# Current_ACS712.net
KiCad netlist of a schematic drawn in EAGLE
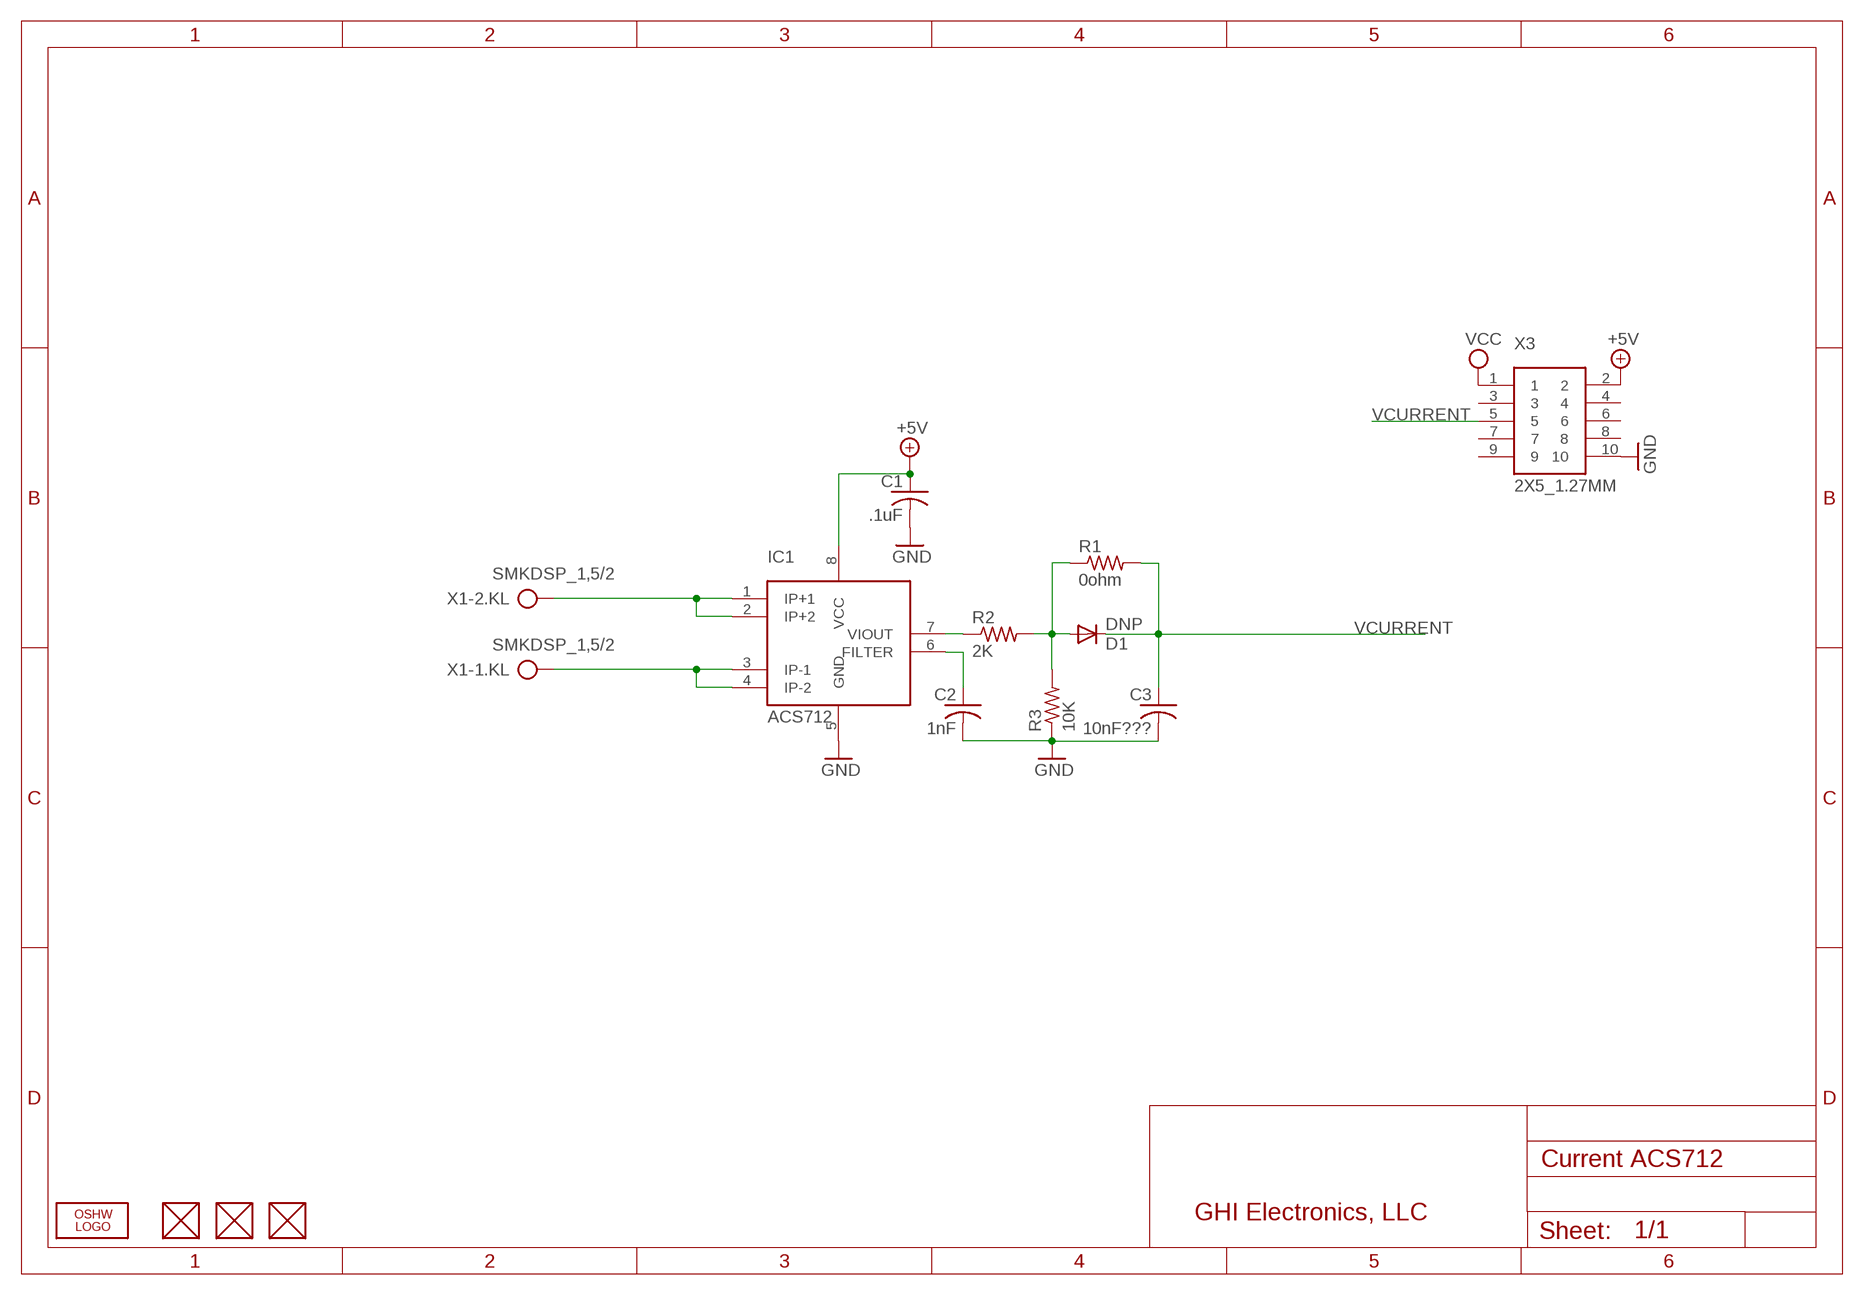
[diagram p0: schematic, sheet 1]

(export (version "E")
  (design (tool "Eeschema 10.0.6"))
  (components
    (comp (ref "C1")
      (value ".1uF")
      (footprint "eagle-import:C0603K")
      (libsource (lib "eagle-import") (part "C-USC0603K"))
    )
    (comp (ref "C2")
      (value "1nF")
      (footprint "eagle-import:C0603K")
      (libsource (lib "eagle-import") (part "C-USC0603K"))
    )
    (comp (ref "C3")
      (value "10nF???")
      (footprint "eagle-import:C0603K")
      (libsource (lib "eagle-import") (part "C-USC0603K"))
    )
    (comp (ref "D1")
      (value "DNP")
      (footprint "eagle-import:SOD323-W")
      (libsource (lib "eagle-import") (part "DIODE-SOD323-W"))
    )
    (comp (ref "FUD1")
      (value "FIDUCIAL")
      (footprint "eagle-import:FIDUCIAL_40MIL")
      (libsource (lib "eagle-import") (part "FIDUCIAL"))
    )
    (comp (ref "FUD2")
      (value "FIDUCIAL")
      (footprint "eagle-import:FIDUCIAL_40MIL")
      (libsource (lib "eagle-import") (part "FIDUCIAL"))
    )
    (comp (ref "FUD3")
      (value "FIDUCIAL")
      (footprint "eagle-import:FIDUCIAL_40MIL")
      (libsource (lib "eagle-import") (part "FIDUCIAL"))
    )
    (comp (ref "IC1")
      (value "ACS712")
      (footprint "eagle-import:SO8")
      (libsource (lib "eagle-import") (part "ACS712"))
    )
    (comp (ref "LOGO2")
      (value "LOGO-OSHW-FILLX0200-NT")
      (footprint "eagle-import:OSHW_FILLX200_NOTEXT")
      (libsource (lib "eagle-import") (part "LOGO-OSHW-FILLX0200-NT"))
    )
    (comp (ref "R1")
      (value "0ohm")
      (footprint "eagle-import:R0603")
      (libsource (lib "eagle-import") (part "R-US_R0603"))
    )
    (comp (ref "R2")
      (value "2K")
      (footprint "eagle-import:R0603")
      (libsource (lib "eagle-import") (part "R-US_R0603"))
    )
    (comp (ref "R3")
      (value "10K")
      (footprint "eagle-import:R0603")
      (libsource (lib "eagle-import") (part "R-US_R0603"))
    )
    (comp (ref "X1")
      (value "SMKDSP_1,5/2")
      (footprint "eagle-import:SMKDSP_1,5_2")
      (libsource (lib "eagle-import") (part "SMKDSP_1,5/2"))
    )
    (comp (ref "X3")
      (value "2X5_1.27MM")
      (footprint "eagle-import:2X5_1.27MM")
      (libsource (lib "eagle-import") (part "2X5_1.27MM"))
    )
  )
  (nets
    (net (code "1") (name "+5V") (class "Default")
      (node (ref "C1") (pin "1") (pinfunction "1_1") (pintype "passive"))
      (node (ref "IC1") (pin "8") (pinfunction "VCC_8") (pintype "bidirectional"))
      (node (ref "X3") (pin "2") (pinfunction "2_2") (pintype "bidirectional"))
    )
    (net (code "2") (name "/VCURRENT") (class "Default")
      (node (ref "C3") (pin "1") (pinfunction "1_1") (pintype "passive"))
      (node (ref "D1") (pin "C") (pinfunction "C_C") (pintype "passive"))
      (node (ref "R1") (pin "2") (pinfunction "2_2") (pintype "passive"))
      (node (ref "X3") (pin "5") (pinfunction "5_5") (pintype "bidirectional"))
    )
    (net (code "3") (name "GND") (class "Default")
      (node (ref "C1") (pin "2") (pinfunction "2_2") (pintype "passive"))
      (node (ref "C2") (pin "2") (pinfunction "2_2") (pintype "passive"))
      (node (ref "C3") (pin "2") (pinfunction "2_2") (pintype "passive"))
      (node (ref "IC1") (pin "5") (pinfunction "GND_5") (pintype "bidirectional"))
      (node (ref "R3") (pin "1") (pinfunction "1_1") (pintype "passive"))
      (node (ref "X3") (pin "10") (pinfunction "10_10") (pintype "bidirectional"))
    )
    (net (code "4") (name "Net-(D1-PadA)") (class "Default")
      (node (ref "D1") (pin "A") (pinfunction "A_A") (pintype "passive"))
      (node (ref "R1") (pin "1") (pinfunction "1_1") (pintype "passive"))
      (node (ref "R2") (pin "2") (pinfunction "2_2") (pintype "passive"))
      (node (ref "R3") (pin "2") (pinfunction "2_2") (pintype "passive"))
    )
    (net (code "5") (name "Net-(IC1-FILTER)") (class "Default")
      (node (ref "C2") (pin "1") (pinfunction "1_1") (pintype "passive"))
      (node (ref "IC1") (pin "6") (pinfunction "FILTER_6") (pintype "bidirectional"))
    )
    (net (code "6") (name "Net-(IC1-IP+1)") (class "Default")
      (node (ref "IC1") (pin "1") (pinfunction "IP+1_1") (pintype "bidirectional"))
      (node (ref "IC1") (pin "2") (pinfunction "IP+2_2") (pintype "bidirectional"))
      (node (ref "X1") (pin "2") (pinfunction "KL_2") (pintype "passive"))
    )
    (net (code "7") (name "Net-(IC1-IP-1)") (class "Default")
      (node (ref "IC1") (pin "3") (pinfunction "IP-1_3") (pintype "bidirectional"))
      (node (ref "IC1") (pin "4") (pinfunction "IP-2_4") (pintype "bidirectional"))
      (node (ref "X1") (pin "1") (pinfunction "KL_1") (pintype "passive"))
    )
    (net (code "8") (name "Net-(IC1-VIOUT)") (class "Default")
      (node (ref "IC1") (pin "7") (pinfunction "VIOUT_7") (pintype "bidirectional"))
      (node (ref "R2") (pin "1") (pinfunction "1_1") (pintype "passive"))
    )
    (net (code "9") (name "VCC") (class "Default")
      (node (ref "X3") (pin "1") (pinfunction "1_1") (pintype "bidirectional"))
    )
    (net (code "10") (name "unconnected-(FUD1-PadP$1)") (class "Default")
      (node (ref "FUD1") (pin "P$1") (pinfunction "P$1_P$1") (pintype "no_connect"))
    )
    (net (code "11") (name "unconnected-(FUD2-PadP$1)") (class "Default")
      (node (ref "FUD2") (pin "P$1") (pinfunction "P$1_P$1") (pintype "no_connect"))
    )
    (net (code "12") (name "unconnected-(FUD3-PadP$1)") (class "Default")
      (node (ref "FUD3") (pin "P$1") (pinfunction "P$1_P$1") (pintype "no_connect"))
    )
    (net (code "13") (name "unconnected-(X3-Pad3)") (class "Default")
      (node (ref "X3") (pin "3") (pinfunction "3_3") (pintype "bidirectional"))
    )
    (net (code "14") (name "unconnected-(X3-Pad4)") (class "Default")
      (node (ref "X3") (pin "4") (pinfunction "4_4") (pintype "bidirectional"))
    )
    (net (code "15") (name "unconnected-(X3-Pad6)") (class "Default")
      (node (ref "X3") (pin "6") (pinfunction "6_6") (pintype "bidirectional"))
    )
    (net (code "16") (name "unconnected-(X3-Pad7)") (class "Default")
      (node (ref "X3") (pin "7") (pinfunction "7_7") (pintype "bidirectional"))
    )
    (net (code "17") (name "unconnected-(X3-Pad8)") (class "Default")
      (node (ref "X3") (pin "8") (pinfunction "8_8") (pintype "bidirectional"))
    )
    (net (code "18") (name "unconnected-(X3-Pad9)") (class "Default")
      (node (ref "X3") (pin "9") (pinfunction "9_9") (pintype "bidirectional"))
    )
  )
)
